# mSD-Shield-Mega_v10.net
KiCad netlist of a schematic drawn in EAGLE
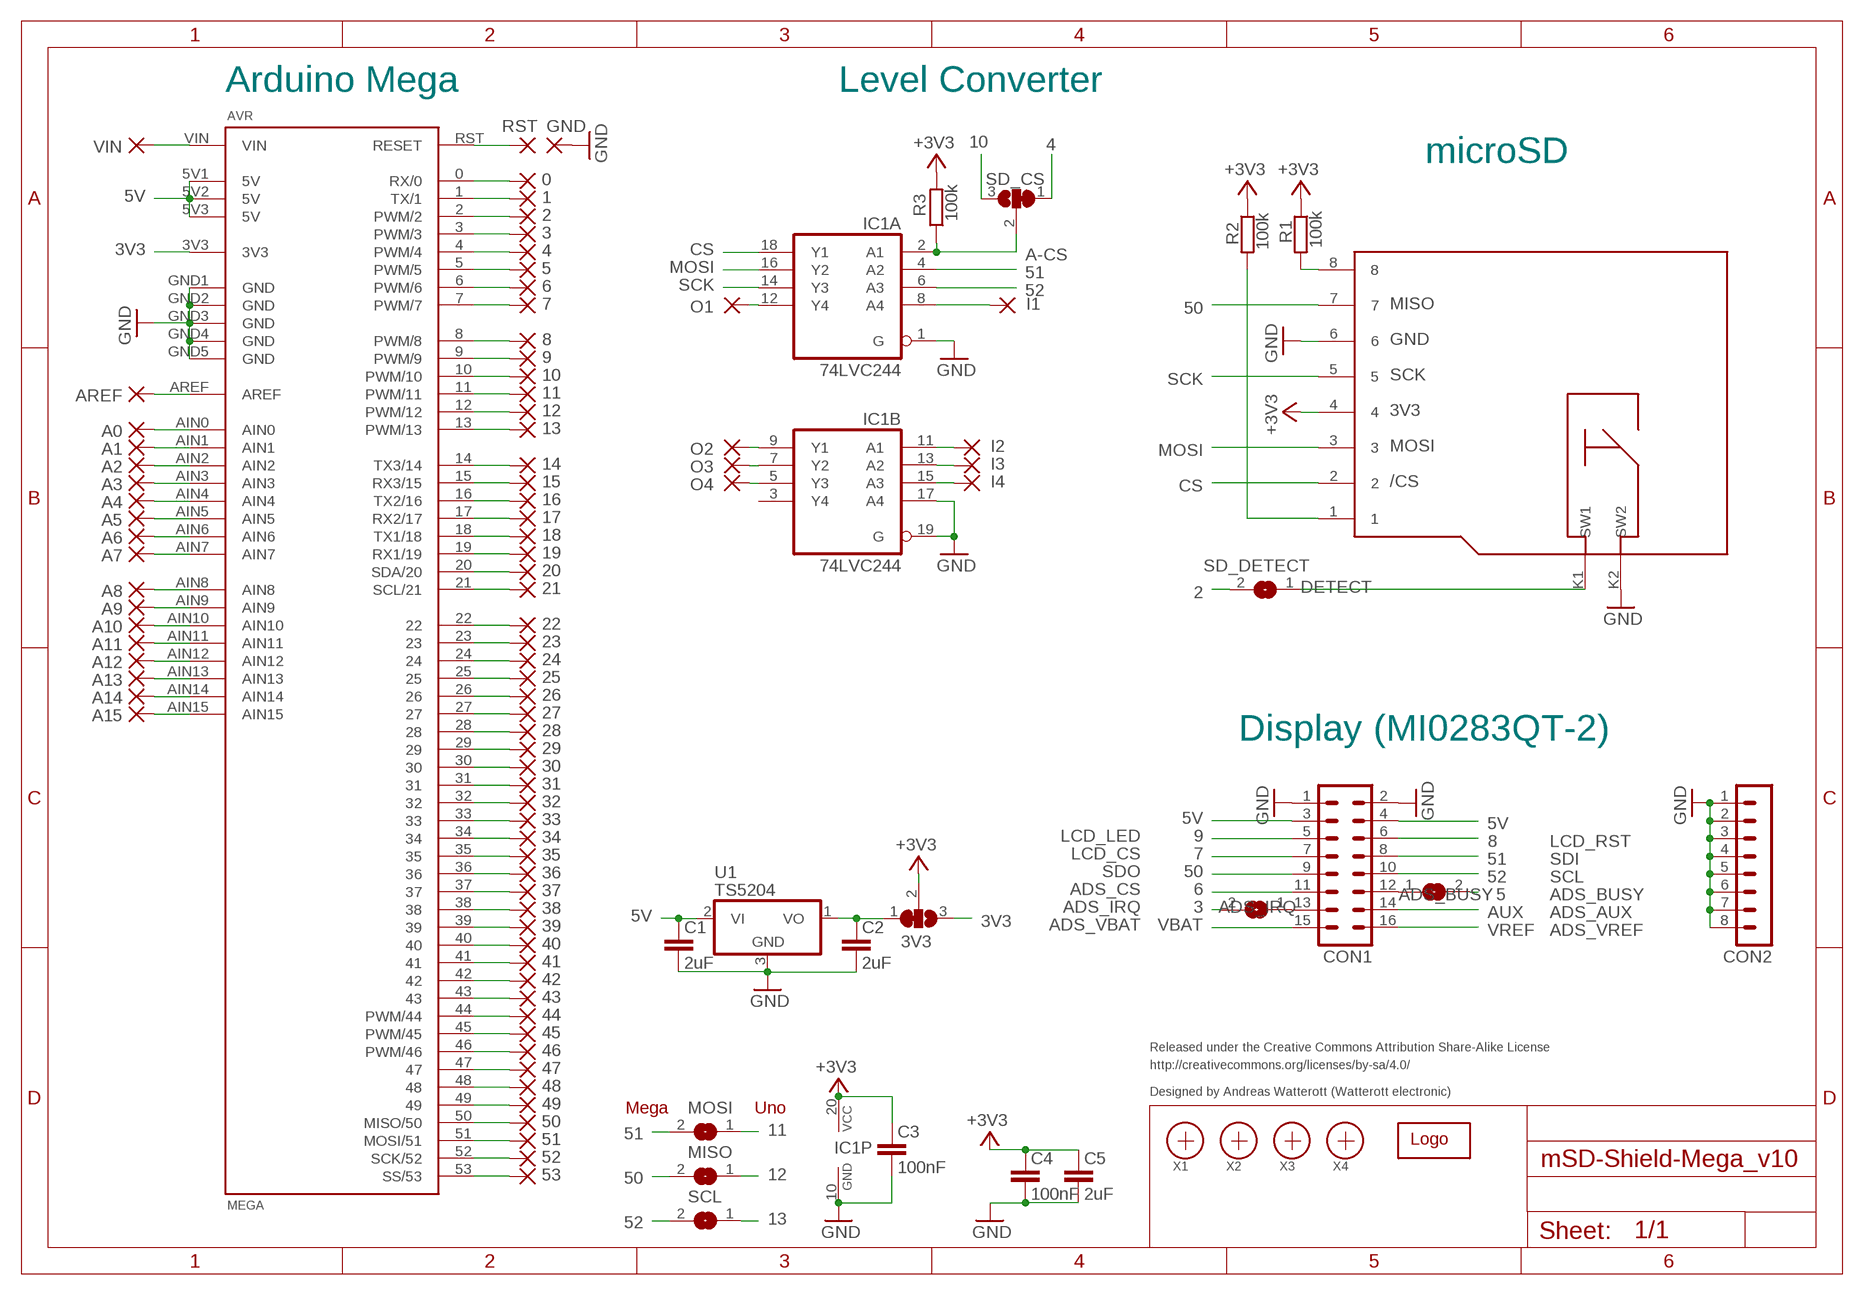
[diagram p0: schematic, sheet 1]

(export (version "E")
  (design (tool "Eeschema 10.0.6"))
  (components
    (comp (ref "0")
      (value "1,6/0,8")
      (footprint "eagle-import:1,6_0,8")
      (libsource (lib "eagle-import") (part "1,6/0,8"))
    )
    (comp (ref "1")
      (value "1,6/0,8")
      (footprint "eagle-import:1,6_0,8")
      (libsource (lib "eagle-import") (part "1,6/0,8"))
    )
    (comp (ref "2")
      (value "1,6/0,8")
      (footprint "eagle-import:1,6_0,8")
      (libsource (lib "eagle-import") (part "1,6/0,8"))
    )
    (comp (ref "3")
      (value "1,6/0,8")
      (footprint "eagle-import:1,6_0,8")
      (libsource (lib "eagle-import") (part "1,6/0,8"))
    )
    (comp (ref "3V3")
      (value "SJ2W")
      (footprint "eagle-import:SJ_2")
      (libsource (lib "eagle-import") (part "SJ2W"))
    )
    (comp (ref "4")
      (value "1,6/0,8")
      (footprint "eagle-import:1,6_0,8")
      (libsource (lib "eagle-import") (part "1,6/0,8"))
    )
    (comp (ref "5")
      (value "1,6/0,8")
      (footprint "eagle-import:1,6_0,8")
      (libsource (lib "eagle-import") (part "1,6/0,8"))
    )
    (comp (ref "6")
      (value "1,6/0,8")
      (footprint "eagle-import:1,6_0,8")
      (libsource (lib "eagle-import") (part "1,6/0,8"))
    )
    (comp (ref "7")
      (value "1,6/0,8")
      (footprint "eagle-import:1,6_0,8")
      (libsource (lib "eagle-import") (part "1,6/0,8"))
    )
    (comp (ref "8")
      (value "1,6/0,8")
      (footprint "eagle-import:1,6_0,8")
      (libsource (lib "eagle-import") (part "1,6/0,8"))
    )
    (comp (ref "9")
      (value "1,6/0,8")
      (footprint "eagle-import:1,6_0,8")
      (libsource (lib "eagle-import") (part "1,6/0,8"))
    )
    (comp (ref "10")
      (value "1,6/0,8")
      (footprint "eagle-import:1,6_0,8")
      (libsource (lib "eagle-import") (part "1,6/0,8"))
    )
    (comp (ref "11")
      (value "1,6/0,8")
      (footprint "eagle-import:1,6_0,8")
      (libsource (lib "eagle-import") (part "1,6/0,8"))
    )
    (comp (ref "12")
      (value "1,6/0,8")
      (footprint "eagle-import:1,6_0,8")
      (libsource (lib "eagle-import") (part "1,6/0,8"))
    )
    (comp (ref "13")
      (value "1,6/0,8")
      (footprint "eagle-import:1,6_0,8")
      (libsource (lib "eagle-import") (part "1,6/0,8"))
    )
    (comp (ref "14")
      (value "1,6/0,8")
      (footprint "eagle-import:1,6_0,8")
      (libsource (lib "eagle-import") (part "1,6/0,8"))
    )
    (comp (ref "15")
      (value "1,6/0,8")
      (footprint "eagle-import:1,6_0,8")
      (libsource (lib "eagle-import") (part "1,6/0,8"))
    )
    (comp (ref "16")
      (value "1,6/0,8")
      (footprint "eagle-import:1,6_0,8")
      (libsource (lib "eagle-import") (part "1,6/0,8"))
    )
    (comp (ref "17")
      (value "1,6/0,8")
      (footprint "eagle-import:1,6_0,8")
      (libsource (lib "eagle-import") (part "1,6/0,8"))
    )
    (comp (ref "18")
      (value "1,6/0,8")
      (footprint "eagle-import:1,6_0,8")
      (libsource (lib "eagle-import") (part "1,6/0,8"))
    )
    (comp (ref "19")
      (value "1,6/0,8")
      (footprint "eagle-import:1,6_0,8")
      (libsource (lib "eagle-import") (part "1,6/0,8"))
    )
    (comp (ref "20")
      (value "1,6/0,8")
      (footprint "eagle-import:1,6_0,8")
      (libsource (lib "eagle-import") (part "1,6/0,8"))
    )
    (comp (ref "21")
      (value "1,6/0,8")
      (footprint "eagle-import:1,6_0,8")
      (libsource (lib "eagle-import") (part "1,6/0,8"))
    )
    (comp (ref "22")
      (value "1,6/0,8")
      (footprint "eagle-import:1,6_0,8")
      (libsource (lib "eagle-import") (part "1,6/0,8"))
    )
    (comp (ref "23")
      (value "1,6/0,8")
      (footprint "eagle-import:1,6_0,8")
      (libsource (lib "eagle-import") (part "1,6/0,8"))
    )
    (comp (ref "24")
      (value "1,6/0,8")
      (footprint "eagle-import:1,6_0,8")
      (libsource (lib "eagle-import") (part "1,6/0,8"))
    )
    (comp (ref "25")
      (value "1,6/0,8")
      (footprint "eagle-import:1,6_0,8")
      (libsource (lib "eagle-import") (part "1,6/0,8"))
    )
    (comp (ref "26")
      (value "1,6/0,8")
      (footprint "eagle-import:1,6_0,8")
      (libsource (lib "eagle-import") (part "1,6/0,8"))
    )
    (comp (ref "27")
      (value "1,6/0,8")
      (footprint "eagle-import:1,6_0,8")
      (libsource (lib "eagle-import") (part "1,6/0,8"))
    )
    (comp (ref "28")
      (value "1,6/0,8")
      (footprint "eagle-import:1,6_0,8")
      (libsource (lib "eagle-import") (part "1,6/0,8"))
    )
    (comp (ref "29")
      (value "1,6/0,8")
      (footprint "eagle-import:1,6_0,8")
      (libsource (lib "eagle-import") (part "1,6/0,8"))
    )
    (comp (ref "30")
      (value "1,6/0,8")
      (footprint "eagle-import:1,6_0,8")
      (libsource (lib "eagle-import") (part "1,6/0,8"))
    )
    (comp (ref "31")
      (value "1,6/0,8")
      (footprint "eagle-import:1,6_0,8")
      (libsource (lib "eagle-import") (part "1,6/0,8"))
    )
    (comp (ref "32")
      (value "1,6/0,8")
      (footprint "eagle-import:1,6_0,8")
      (libsource (lib "eagle-import") (part "1,6/0,8"))
    )
    (comp (ref "33")
      (value "1,6/0,8")
      (footprint "eagle-import:1,6_0,8")
      (libsource (lib "eagle-import") (part "1,6/0,8"))
    )
    (comp (ref "34")
      (value "1,6/0,8")
      (footprint "eagle-import:1,6_0,8")
      (libsource (lib "eagle-import") (part "1,6/0,8"))
    )
    (comp (ref "35")
      (value "1,6/0,8")
      (footprint "eagle-import:1,6_0,8")
      (libsource (lib "eagle-import") (part "1,6/0,8"))
    )
    (comp (ref "36")
      (value "1,6/0,8")
      (footprint "eagle-import:1,6_0,8")
      (libsource (lib "eagle-import") (part "1,6/0,8"))
    )
    (comp (ref "37")
      (value "1,6/0,8")
      (footprint "eagle-import:1,6_0,8")
      (libsource (lib "eagle-import") (part "1,6/0,8"))
    )
    (comp (ref "38")
      (value "1,6/0,8")
      (footprint "eagle-import:1,6_0,8")
      (libsource (lib "eagle-import") (part "1,6/0,8"))
    )
    (comp (ref "39")
      (value "1,6/0,8")
      (footprint "eagle-import:1,6_0,8")
      (libsource (lib "eagle-import") (part "1,6/0,8"))
    )
    (comp (ref "40")
      (value "1,6/0,8")
      (footprint "eagle-import:1,6_0,8")
      (libsource (lib "eagle-import") (part "1,6/0,8"))
    )
    (comp (ref "41")
      (value "1,6/0,8")
      (footprint "eagle-import:1,6_0,8")
      (libsource (lib "eagle-import") (part "1,6/0,8"))
    )
    (comp (ref "42")
      (value "1,6/0,8")
      (footprint "eagle-import:1,6_0,8")
      (libsource (lib "eagle-import") (part "1,6/0,8"))
    )
    (comp (ref "43")
      (value "1,6/0,8")
      (footprint "eagle-import:1,6_0,8")
      (libsource (lib "eagle-import") (part "1,6/0,8"))
    )
    (comp (ref "44")
      (value "1,6/0,8")
      (footprint "eagle-import:1,6_0,8")
      (libsource (lib "eagle-import") (part "1,6/0,8"))
    )
    (comp (ref "45")
      (value "1,6/0,8")
      (footprint "eagle-import:1,6_0,8")
      (libsource (lib "eagle-import") (part "1,6/0,8"))
    )
    (comp (ref "46")
      (value "1,6/0,8")
      (footprint "eagle-import:1,6_0,8")
      (libsource (lib "eagle-import") (part "1,6/0,8"))
    )
    (comp (ref "47")
      (value "1,6/0,8")
      (footprint "eagle-import:1,6_0,8")
      (libsource (lib "eagle-import") (part "1,6/0,8"))
    )
    (comp (ref "48")
      (value "1,6/0,8")
      (footprint "eagle-import:1,6_0,8")
      (libsource (lib "eagle-import") (part "1,6/0,8"))
    )
    (comp (ref "49")
      (value "1,6/0,8")
      (footprint "eagle-import:1,6_0,8")
      (libsource (lib "eagle-import") (part "1,6/0,8"))
    )
    (comp (ref "50")
      (value "1,6/0,8")
      (footprint "eagle-import:1,6_0,8")
      (libsource (lib "eagle-import") (part "1,6/0,8"))
    )
    (comp (ref "51")
      (value "1,6/0,8")
      (footprint "eagle-import:1,6_0,8")
      (libsource (lib "eagle-import") (part "1,6/0,8"))
    )
    (comp (ref "52")
      (value "1,6/0,8")
      (footprint "eagle-import:1,6_0,8")
      (libsource (lib "eagle-import") (part "1,6/0,8"))
    )
    (comp (ref "53")
      (value "1,6/0,8")
      (footprint "eagle-import:1,6_0,8")
      (libsource (lib "eagle-import") (part "1,6/0,8"))
    )
    (comp (ref "A0")
      (value "1,6/0,8")
      (footprint "eagle-import:1,6_0,8")
      (libsource (lib "eagle-import") (part "1,6/0,8"))
    )
    (comp (ref "A1")
      (value "1,6/0,8")
      (footprint "eagle-import:1,6_0,8")
      (libsource (lib "eagle-import") (part "1,6/0,8"))
    )
    (comp (ref "A2")
      (value "1,6/0,8")
      (footprint "eagle-import:1,6_0,8")
      (libsource (lib "eagle-import") (part "1,6/0,8"))
    )
    (comp (ref "A3")
      (value "1,6/0,8")
      (footprint "eagle-import:1,6_0,8")
      (libsource (lib "eagle-import") (part "1,6/0,8"))
    )
    (comp (ref "A4")
      (value "1,6/0,8")
      (footprint "eagle-import:1,6_0,8")
      (libsource (lib "eagle-import") (part "1,6/0,8"))
    )
    (comp (ref "A5")
      (value "1,6/0,8")
      (footprint "eagle-import:1,6_0,8")
      (libsource (lib "eagle-import") (part "1,6/0,8"))
    )
    (comp (ref "A6")
      (value "1,6/0,8")
      (footprint "eagle-import:1,6_0,8")
      (libsource (lib "eagle-import") (part "1,6/0,8"))
    )
    (comp (ref "A7")
      (value "1,6/0,8")
      (footprint "eagle-import:1,6_0,8")
      (libsource (lib "eagle-import") (part "1,6/0,8"))
    )
    (comp (ref "A8")
      (value "1,6/0,8")
      (footprint "eagle-import:1,6_0,8")
      (libsource (lib "eagle-import") (part "1,6/0,8"))
    )
    (comp (ref "A9")
      (value "1,6/0,8")
      (footprint "eagle-import:1,6_0,8")
      (libsource (lib "eagle-import") (part "1,6/0,8"))
    )
    (comp (ref "A10")
      (value "1,6/0,8")
      (footprint "eagle-import:1,6_0,8")
      (libsource (lib "eagle-import") (part "1,6/0,8"))
    )
    (comp (ref "A11")
      (value "1,6/0,8")
      (footprint "eagle-import:1,6_0,8")
      (libsource (lib "eagle-import") (part "1,6/0,8"))
    )
    (comp (ref "A12")
      (value "1,6/0,8")
      (footprint "eagle-import:1,6_0,8")
      (libsource (lib "eagle-import") (part "1,6/0,8"))
    )
    (comp (ref "A13")
      (value "1,6/0,8")
      (footprint "eagle-import:1,6_0,8")
      (libsource (lib "eagle-import") (part "1,6/0,8"))
    )
    (comp (ref "A14")
      (value "1,6/0,8")
      (footprint "eagle-import:1,6_0,8")
      (libsource (lib "eagle-import") (part "1,6/0,8"))
    )
    (comp (ref "A15")
      (value "1,6/0,8")
      (footprint "eagle-import:1,6_0,8")
      (libsource (lib "eagle-import") (part "1,6/0,8"))
    )
    (comp (ref "ADS_BUSY")
      (value "SJ")
      (footprint "eagle-import:SJ")
      (libsource (lib "eagle-import") (part "SJ"))
    )
    (comp (ref "ADS_IRQ")
      (value "SJ")
      (footprint "eagle-import:SJ")
      (libsource (lib "eagle-import") (part "SJ"))
    )
    (comp (ref "AREF")
      (value "1,6/0,8")
      (footprint "eagle-import:1,6_0,8")
      (libsource (lib "eagle-import") (part "1,6/0,8"))
    )
    (comp (ref "AVR")
      (value "MEGA")
      (footprint "eagle-import:MEGA")
      (libsource (lib "eagle-import") (part "MEGA"))
    )
    (comp (ref "C1")
      (value "2uF")
      (footprint "eagle-import:C0805")
      (libsource (lib "eagle-import") (part "C-EUC0805"))
    )
    (comp (ref "C2")
      (value "2uF")
      (footprint "eagle-import:C0805")
      (libsource (lib "eagle-import") (part "C-EUC0805"))
    )
    (comp (ref "C3")
      (value "100nF")
      (footprint "eagle-import:C0603")
      (libsource (lib "eagle-import") (part "C-EUC0603"))
    )
    (comp (ref "C4")
      (value "100nF")
      (footprint "eagle-import:C0603")
      (libsource (lib "eagle-import") (part "C-EUC0603"))
    )
    (comp (ref "C5")
      (value "2uF")
      (footprint "eagle-import:C0603")
      (libsource (lib "eagle-import") (part "C-EUC0603"))
    )
    (comp (ref "CON1")
      (value "MA08-2")
      (footprint "eagle-import:MA08-2")
      (libsource (lib "eagle-import") (part "MA08-2"))
    )
    (comp (ref "CON2")
      (value "MA08-1")
      (footprint "eagle-import:MA08-1")
      (libsource (lib "eagle-import") (part "MA08-1"))
    )
    (comp (ref "GND")
      (value "SMD2")
      (footprint "eagle-import:SMD1,27-2,54")
      (libsource (lib "eagle-import") (part "SMD2"))
    )
    (comp (ref "I1")
      (value "SMD2")
      (footprint "eagle-import:SMD1,27-2,54")
      (libsource (lib "eagle-import") (part "SMD2"))
    )
    (comp (ref "I2")
      (value "SMD2")
      (footprint "eagle-import:SMD1,27-2,54")
      (libsource (lib "eagle-import") (part "SMD2"))
    )
    (comp (ref "I3")
      (value "SMD2")
      (footprint "eagle-import:SMD1,27-2,54")
      (libsource (lib "eagle-import") (part "SMD2"))
    )
    (comp (ref "I4")
      (value "SMD2")
      (footprint "eagle-import:SMD1,27-2,54")
      (libsource (lib "eagle-import") (part "SMD2"))
    )
    (comp (ref "IC1")
      (value "74LVC244")
      (footprint "eagle-import:SO20W")
      (libsource (lib "eagle-import") (part "74244DWHC"))
    )
    (comp (ref "MISO")
      (value "SJ")
      (footprint "eagle-import:SJ")
      (libsource (lib "eagle-import") (part "SJ"))
    )
    (comp (ref "MOSI")
      (value "SJ")
      (footprint "eagle-import:SJ")
      (libsource (lib "eagle-import") (part "SJ"))
    )
    (comp (ref "O1")
      (value "SMD2")
      (footprint "eagle-import:SMD1,27-2,54")
      (libsource (lib "eagle-import") (part "SMD2"))
    )
    (comp (ref "O2")
      (value "SMD2")
      (footprint "eagle-import:SMD1,27-2,54")
      (libsource (lib "eagle-import") (part "SMD2"))
    )
    (comp (ref "O3")
      (value "SMD2")
      (footprint "eagle-import:SMD1,27-2,54")
      (libsource (lib "eagle-import") (part "SMD2"))
    )
    (comp (ref "O4")
      (value "SMD2")
      (footprint "eagle-import:SMD1,27-2,54")
      (libsource (lib "eagle-import") (part "SMD2"))
    )
    (comp (ref "R1")
      (value "100k")
      (footprint "eagle-import:R0603")
      (libsource (lib "eagle-import") (part "R-EU_R0603"))
    )
    (comp (ref "R2")
      (value "100k")
      (footprint "eagle-import:R0603")
      (libsource (lib "eagle-import") (part "R-EU_R0603"))
    )
    (comp (ref "R3")
      (value "100k")
      (footprint "eagle-import:R0603")
      (libsource (lib "eagle-import") (part "R-EU_R0603"))
    )
    (comp (ref "RST")
      (value "SMD2")
      (footprint "eagle-import:SMD1,27-2,54")
      (libsource (lib "eagle-import") (part "SMD2"))
    )
    (comp (ref "SCL") (value "SJ") (footprint "eagle-import:SJ") (libsource (lib "eagle-import") (part "SJ")))
    (comp (ref "SD_CS")
      (value "SJ2W")
      (footprint "eagle-import:SJ_2")
      (libsource (lib "eagle-import") (part "SJ2W"))
    )
    (comp (ref "SD_DETECT")
      (value "SJ")
      (footprint "eagle-import:SJ")
      (libsource (lib "eagle-import") (part "SJ"))
    )
    (comp (ref "U$1")
      (value "WE-LOGO")
      (footprint "eagle-import:WE-LOGO")
      (libsource (lib "eagle-import") (part "WE-LOGO"))
    )
    (comp (ref "U1")
      (value "TS5204")
      (footprint "eagle-import:SOT23")
      (libsource (lib "eagle-import") (part "TS5204"))
    )
    (comp (ref "VIN")
      (value "1,6/0,8")
      (footprint "eagle-import:1,6_0,8")
      (libsource (lib "eagle-import") (part "1,6/0,8"))
    )
    (comp (ref "X1")
      (value "PASSER")
      (footprint "eagle-import:PASSER")
      (libsource (lib "eagle-import") (part "PASSER"))
    )
    (comp (ref "X2")
      (value "PASSER")
      (footprint "eagle-import:PASSER")
      (libsource (lib "eagle-import") (part "PASSER"))
    )
    (comp (ref "X3")
      (value "PASSER")
      (footprint "eagle-import:PASSER")
      (libsource (lib "eagle-import") (part "PASSER"))
    )
    (comp (ref "X4")
      (value "PASSER")
      (footprint "eagle-import:PASSER")
      (libsource (lib "eagle-import") (part "PASSER"))
    )
    (comp (ref "X5")
      (value "MICRO-SD")
      (footprint "eagle-import:MICRO-SD")
      (libsource (lib "eagle-import") (part "MICRO-SD"))
    )
  )
  (nets
    (net (code "1") (name "+3V3") (class "Default")
      (node (ref "3V3") (pin "2") (pinfunction "2_2") (pintype "passive"))
      (node (ref "C3") (pin "1") (pinfunction "1_1") (pintype "passive"))
      (node (ref "C4") (pin "1") (pinfunction "1_1") (pintype "passive"))
      (node (ref "C5") (pin "1") (pinfunction "1_1") (pintype "passive"))
      (node (ref "IC1") (pin "20") (pinfunction "VCC_20") (pintype "power_in"))
      (node (ref "R1") (pin "1") (pinfunction "1_1") (pintype "passive"))
      (node (ref "R2") (pin "1") (pinfunction "1_1") (pintype "passive"))
      (node (ref "R3") (pin "2") (pinfunction "2_2") (pintype "passive"))
      (node (ref "X5") (pin "4") (pinfunction "4_4") (pintype "bidirectional"))
    )
    (net (code "2") (name "/2") (class "Default")
      (node (ref "2") (pin "1") (pinfunction "P_1") (pintype "passive"))
      (node (ref "AVR") (pin "2") (pinfunction "PWM/2_2") (pintype "bidirectional"))
      (node (ref "SD_DETECT") (pin "2") (pinfunction "2_2") (pintype "passive"))
    )
    (net (code "3") (name "/3") (class "Default")
      (node (ref "3") (pin "1") (pinfunction "P_1") (pintype "passive"))
      (node (ref "ADS_IRQ") (pin "2") (pinfunction "2_2") (pintype "passive"))
      (node (ref "AVR") (pin "3") (pinfunction "PWM/3_3") (pintype "bidirectional"))
    )
    (net (code "4") (name "/3V3") (class "Default")
      (node (ref "3V3") (pin "3") (pinfunction "3_3") (pintype "passive"))
      (node (ref "AVR") (pin "3V3") (pinfunction "3V3_3V3") (pintype "power_in"))
    )
    (net (code "5") (name "/4") (class "Default")
      (node (ref "4") (pin "1") (pinfunction "P_1") (pintype "passive"))
      (node (ref "AVR") (pin "4") (pinfunction "PWM/4_4") (pintype "bidirectional"))
      (node (ref "SD_CS") (pin "1") (pinfunction "1_1") (pintype "passive"))
    )
    (net (code "6") (name "/5") (class "Default")
      (node (ref "5") (pin "1") (pinfunction "P_1") (pintype "passive"))
      (node (ref "ADS_BUSY") (pin "2") (pinfunction "2_2") (pintype "passive"))
      (node (ref "AVR") (pin "5") (pinfunction "PWM/5_5") (pintype "bidirectional"))
    )
    (net (code "7") (name "/5V") (class "Default")
      (node (ref "AVR") (pin "5V1") (pinfunction "5V_5V1") (pintype "power_in"))
      (node (ref "AVR") (pin "5V2") (pinfunction "5V_5V2") (pintype "power_in"))
      (node (ref "AVR") (pin "5V3") (pinfunction "5V_5V3") (pintype "power_in"))
      (node (ref "C1") (pin "1") (pinfunction "1_1") (pintype "passive"))
      (node (ref "CON1") (pin "3") (pinfunction "3_3") (pintype "passive"))
      (node (ref "CON1") (pin "4") (pinfunction "4_4") (pintype "passive"))
      (node (ref "U1") (pin "2") (pinfunction "VI_2") (pintype "input"))
    )
    (net (code "8") (name "/6") (class "Default")
      (node (ref "6") (pin "1") (pinfunction "P_1") (pintype "passive"))
      (node (ref "AVR") (pin "6") (pinfunction "PWM/6_6") (pintype "bidirectional"))
      (node (ref "CON1") (pin "11") (pinfunction "11_11") (pintype "passive"))
    )
    (net (code "9") (name "/7") (class "Default")
      (node (ref "7") (pin "1") (pinfunction "P_1") (pintype "passive"))
      (node (ref "AVR") (pin "7") (pinfunction "PWM/7_7") (pintype "bidirectional"))
      (node (ref "CON1") (pin "7") (pinfunction "7_7") (pintype "passive"))
    )
    (net (code "10") (name "/8") (class "Default")
      (node (ref "8") (pin "1") (pinfunction "P_1") (pintype "passive"))
      (node (ref "AVR") (pin "8") (pinfunction "PWM/8_8") (pintype "bidirectional"))
      (node (ref "CON1") (pin "6") (pinfunction "6_6") (pintype "passive"))
    )
    (net (code "11") (name "/9") (class "Default")
      (node (ref "9") (pin "1") (pinfunction "P_1") (pintype "passive"))
      (node (ref "AVR") (pin "9") (pinfunction "PWM/9_9") (pintype "bidirectional"))
      (node (ref "CON1") (pin "5") (pinfunction "5_5") (pintype "passive"))
    )
    (net (code "12") (name "/10") (class "Default")
      (node (ref "10") (pin "1") (pinfunction "P_1") (pintype "passive"))
      (node (ref "AVR") (pin "10") (pinfunction "PWM/10_10") (pintype "bidirectional"))
      (node (ref "SD_CS") (pin "3") (pinfunction "3_3") (pintype "passive"))
    )
    (net (code "13") (name "/11") (class "Default")
      (node (ref "11") (pin "1") (pinfunction "P_1") (pintype "passive"))
      (node (ref "AVR") (pin "11") (pinfunction "PWM/11_11") (pintype "bidirectional"))
      (node (ref "MOSI") (pin "1") (pinfunction "1_1") (pintype "passive"))
    )
    (net (code "14") (name "/12") (class "Default")
      (node (ref "12") (pin "1") (pinfunction "P_1") (pintype "passive"))
      (node (ref "AVR") (pin "12") (pinfunction "PWM/12_12") (pintype "bidirectional"))
      (node (ref "MISO") (pin "1") (pinfunction "1_1") (pintype "passive"))
    )
    (net (code "15") (name "/13") (class "Default")
      (node (ref "13") (pin "1") (pinfunction "P_1") (pintype "passive"))
      (node (ref "AVR") (pin "13") (pinfunction "PWM/13_13") (pintype "bidirectional"))
      (node (ref "SCL") (pin "1") (pinfunction "1_1") (pintype "passive"))
    )
    (net (code "16") (name "/50") (class "Default")
      (node (ref "50") (pin "1") (pinfunction "P_1") (pintype "passive"))
      (node (ref "AVR") (pin "50") (pinfunction "MISO/50_50") (pintype "bidirectional"))
      (node (ref "CON1") (pin "9") (pinfunction "9_9") (pintype "passive"))
      (node (ref "MISO") (pin "2") (pinfunction "2_2") (pintype "passive"))
      (node (ref "X5") (pin "7") (pinfunction "7_7") (pintype "bidirectional"))
    )
    (net (code "17") (name "/51") (class "Default")
      (node (ref "51") (pin "1") (pinfunction "P_1") (pintype "passive"))
      (node (ref "AVR") (pin "51") (pinfunction "MOSI/51_51") (pintype "bidirectional"))
      (node (ref "CON1") (pin "8") (pinfunction "8_8") (pintype "passive"))
      (node (ref "IC1") (pin "4") (pinfunction "A2_4") (pintype "input"))
      (node (ref "MOSI") (pin "2") (pinfunction "2_2") (pintype "passive"))
    )
    (net (code "18") (name "/52") (class "Default")
      (node (ref "52") (pin "1") (pinfunction "P_1") (pintype "passive"))
      (node (ref "AVR") (pin "52") (pinfunction "SCK/52_52") (pintype "bidirectional"))
      (node (ref "CON1") (pin "10") (pinfunction "10_10") (pintype "passive"))
      (node (ref "IC1") (pin "6") (pinfunction "A3_6") (pintype "input"))
      (node (ref "SCL") (pin "2") (pinfunction "2_2") (pintype "passive"))
    )
    (net (code "19") (name "/A-CS") (class "Default")
      (node (ref "IC1") (pin "2") (pinfunction "A1_2") (pintype "input"))
      (node (ref "R3") (pin "1") (pinfunction "1_1") (pintype "passive"))
      (node (ref "SD_CS") (pin "2") (pinfunction "2_2") (pintype "passive"))
    )
    (net (code "20") (name "/AUX") (class "Default")
      (node (ref "CON1") (pin "14") (pinfunction "14_14") (pintype "passive"))
    )
    (net (code "21") (name "/CS") (class "Default")
      (node (ref "IC1") (pin "18") (pinfunction "Y1_18") (pintype "tri_state"))
      (node (ref "X5") (pin "2") (pinfunction "2_2") (pintype "bidirectional"))
    )
    (net (code "22") (name "/DETECT") (class "Default")
      (node (ref "SD_DETECT") (pin "1") (pinfunction "1_1") (pintype "passive"))
      (node (ref "X5") (pin "K1") (pinfunction "SW1_K1") (pintype "bidirectional"))
    )
    (net (code "23") (name "/MOSI") (class "Default")
      (node (ref "IC1") (pin "16") (pinfunction "Y2_16") (pintype "tri_state"))
      (node (ref "X5") (pin "3") (pinfunction "3_3") (pintype "bidirectional"))
    )
    (net (code "24") (name "/SCK") (class "Default")
      (node (ref "IC1") (pin "14") (pinfunction "Y3_14") (pintype "tri_state"))
      (node (ref "X5") (pin "5") (pinfunction "5_5") (pintype "bidirectional"))
    )
    (net (code "25") (name "/VBAT") (class "Default")
      (node (ref "CON1") (pin "15") (pinfunction "15_15") (pintype "passive"))
    )
    (net (code "26") (name "/VREF") (class "Default")
      (node (ref "CON1") (pin "16") (pinfunction "16_16") (pintype "passive"))
    )
    (net (code "27") (name "GND") (class "Default")
      (node (ref "AVR") (pin "GND1") (pinfunction "GND_GND1") (pintype "power_in"))
      (node (ref "AVR") (pin "GND2") (pinfunction "GND_GND2") (pintype "power_in"))
      (node (ref "AVR") (pin "GND3") (pinfunction "GND_GND3") (pintype "power_in"))
      (node (ref "AVR") (pin "GND4") (pinfunction "GND_GND4") (pintype "power_in"))
      (node (ref "AVR") (pin "GND5") (pinfunction "GND_GND5") (pintype "power_in"))
      (node (ref "C1") (pin "2") (pinfunction "2_2") (pintype "passive"))
      (node (ref "C2") (pin "2") (pinfunction "2_2") (pintype "passive"))
      (node (ref "C3") (pin "2") (pinfunction "2_2") (pintype "passive"))
      (node (ref "C4") (pin "2") (pinfunction "2_2") (pintype "passive"))
      (node (ref "C5") (pin "2") (pinfunction "2_2") (pintype "passive"))
      (node (ref "CON1") (pin "1") (pinfunction "1_1") (pintype "passive"))
      (node (ref "CON1") (pin "2") (pinfunction "2_2") (pintype "passive"))
      (node (ref "CON2") (pin "1") (pinfunction "1_1") (pintype "passive"))
      (node (ref "CON2") (pin "2") (pinfunction "2_2") (pintype "passive"))
      (node (ref "CON2") (pin "3") (pinfunction "3_3") (pintype "passive"))
      (node (ref "CON2") (pin "4") (pinfunction "4_4") (pintype "passive"))
      (node (ref "CON2") (pin "5") (pinfunction "5_5") (pintype "passive"))
      (node (ref "CON2") (pin "6") (pinfunction "6_6") (pintype "passive"))
      (node (ref "CON2") (pin "7") (pinfunction "7_7") (pintype "passive"))
      (node (ref "CON2") (pin "8") (pinfunction "8_8") (pintype "passive"))
      (node (ref "GND") (pin "1") (pinfunction "P_1") (pintype "passive"))
      (node (ref "IC1") (pin "1") (pinfunction "G_1") (pintype "input"))
      (node (ref "IC1") (pin "10") (pinfunction "GND_10") (pintype "power_in"))
      (node (ref "IC1") (pin "17") (pinfunction "A4_17") (pintype "input"))
      (node (ref "IC1") (pin "19") (pinfunction "G_19") (pintype "input"))
      (node (ref "U1") (pin "3") (pinfunction "GND_3") (pintype "passive"))
      (node (ref "X5") (pin "6") (pinfunction "6_6") (pintype "bidirectional"))
      (node (ref "X5") (pin "K2") (pinfunction "SW2_K2") (pintype "bidirectional"))
    )
    (net (code "28") (name "Net-(0-P)") (class "Default")
      (node (ref "0") (pin "1") (pinfunction "P_1") (pintype "passive"))
      (node (ref "AVR") (pin "0") (pinfunction "RX/0_0") (pintype "bidirectional"))
    )
    (net (code "29") (name "Net-(1-P)") (class "Default")
      (node (ref "1") (pin "1") (pinfunction "P_1") (pintype "passive"))
      (node (ref "AVR") (pin "1") (pinfunction "TX/1_1") (pintype "bidirectional"))
    )
    (net (code "30") (name "Net-(14-P)") (class "Default")
      (node (ref "14") (pin "1") (pinfunction "P_1") (pintype "passive"))
      (node (ref "AVR") (pin "14") (pinfunction "TX3/14_14") (pintype "bidirectional"))
    )
    (net (code "31") (name "Net-(15-P)") (class "Default")
      (node (ref "15") (pin "1") (pinfunction "P_1") (pintype "passive"))
      (node (ref "AVR") (pin "15") (pinfunction "RX3/15_15") (pintype "bidirectional"))
    )
    (net (code "32") (name "Net-(16-P)") (class "Default")
      (node (ref "16") (pin "1") (pinfunction "P_1") (pintype "passive"))
      (node (ref "AVR") (pin "16") (pinfunction "TX2/16_16") (pintype "bidirectional"))
    )
    (net (code "33") (name "Net-(17-P)") (class "Default")
      (node (ref "17") (pin "1") (pinfunction "P_1") (pintype "passive"))
      (node (ref "AVR") (pin "17") (pinfunction "RX2/17_17") (pintype "bidirectional"))
    )
    (net (code "34") (name "Net-(18-P)") (class "Default")
      (node (ref "18") (pin "1") (pinfunction "P_1") (pintype "passive"))
      (node (ref "AVR") (pin "18") (pinfunction "TX1/18_18") (pintype "bidirectional"))
    )
    (net (code "35") (name "Net-(19-P)") (class "Default")
      (node (ref "19") (pin "1") (pinfunction "P_1") (pintype "passive"))
      (node (ref "AVR") (pin "19") (pinfunction "RX1/19_19") (pintype "bidirectional"))
    )
    (net (code "36") (name "Net-(20-P)") (class "Default")
      (node (ref "20") (pin "1") (pinfunction "P_1") (pintype "passive"))
      (node (ref "AVR") (pin "20") (pinfunction "SDA/20_20") (pintype "bidirectional"))
    )
    (net (code "37") (name "Net-(21-P)") (class "Default")
      (node (ref "21") (pin "1") (pinfunction "P_1") (pintype "passive"))
      (node (ref "AVR") (pin "21") (pinfunction "SCL/21_21") (pintype "bidirectional"))
    )
    (net (code "38") (name "Net-(22-P)") (class "Default")
      (node (ref "22") (pin "1") (pinfunction "P_1") (pintype "passive"))
      (node (ref "AVR") (pin "22") (pinfunction "22_22") (pintype "bidirectional"))
    )
    (net (code "39") (name "Net-(23-P)") (class "Default")
      (node (ref "23") (pin "1") (pinfunction "P_1") (pintype "passive"))
      (node (ref "AVR") (pin "23") (pinfunction "23_23") (pintype "bidirectional"))
    )
    (net (code "40") (name "Net-(24-P)") (class "Default")
      (node (ref "24") (pin "1") (pinfunction "P_1") (pintype "passive"))
      (node (ref "AVR") (pin "24") (pinfunction "24_24") (pintype "bidirectional"))
    )
    (net (code "41") (name "Net-(25-P)") (class "Default")
      (node (ref "25") (pin "1") (pinfunction "P_1") (pintype "passive"))
      (node (ref "AVR") (pin "25") (pinfunction "25_25") (pintype "bidirectional"))
    )
    (net (code "42") (name "Net-(26-P)") (class "Default")
      (node (ref "26") (pin "1") (pinfunction "P_1") (pintype "passive"))
      (node (ref "AVR") (pin "26") (pinfunction "26_26") (pintype "bidirectional"))
    )
    (net (code "43") (name "Net-(27-P)") (class "Default")
      (node (ref "27") (pin "1") (pinfunction "P_1") (pintype "passive"))
      (node (ref "AVR") (pin "27") (pinfunction "27_27") (pintype "bidirectional"))
    )
    (net (code "44") (name "Net-(28-P)") (class "Default")
      (node (ref "28") (pin "1") (pinfunction "P_1") (pintype "passive"))
      (node (ref "AVR") (pin "28") (pinfunction "28_28") (pintype "bidirectional"))
    )
    (net (code "45") (name "Net-(29-P)") (class "Default")
      (node (ref "29") (pin "1") (pinfunction "P_1") (pintype "passive"))
      (node (ref "AVR") (pin "29") (pinfunction "29_29") (pintype "bidirectional"))
    )
    (net (code "46") (name "Net-(30-P)") (class "Default")
      (node (ref "30") (pin "1") (pinfunction "P_1") (pintype "passive"))
      (node (ref "AVR") (pin "30") (pinfunction "30_30") (pintype "bidirectional"))
    )
    (net (code "47") (name "Net-(31-P)") (class "Default")
      (node (ref "31") (pin "1") (pinfunction "P_1") (pintype "passive"))
      (node (ref "AVR") (pin "31") (pinfunction "31_31") (pintype "bidirectional"))
    )
    (net (code "48") (name "Net-(32-P)") (class "Default")
      (node (ref "32") (pin "1") (pinfunction "P_1") (pintype "passive"))
      (node (ref "AVR") (pin "32") (pinfunction "32_32") (pintype "bidirectional"))
    )
    (net (code "49") (name "Net-(33-P)") (class "Default")
      (node (ref "33") (pin "1") (pinfunction "P_1") (pintype "passive"))
      (node (ref "AVR") (pin "33") (pinfunction "33_33") (pintype "bidirectional"))
    )
    (net (code "50") (name "Net-(34-P)") (class "Default")
      (node (ref "34") (pin "1") (pinfunction "P_1") (pintype "passive"))
      (node (ref "AVR") (pin "34") (pinfunction "34_34") (pintype "bidirectional"))
    )
    (net (code "51") (name "Net-(35-P)") (class "Default")
      (node (ref "35") (pin "1") (pinfunction "P_1") (pintype "passive"))
      (node (ref "AVR") (pin "35") (pinfunction "35_35") (pintype "bidirectional"))
    )
    (net (code "52") (name "Net-(36-P)") (class "Default")
      (node (ref "36") (pin "1") (pinfunction "P_1") (pintype "passive"))
      (node (ref "AVR") (pin "36") (pinfunction "36_36") (pintype "bidirectional"))
    )
    (net (code "53") (name "Net-(37-P)") (class "Default")
      (node (ref "37") (pin "1") (pinfunction "P_1") (pintype "passive"))
      (node (ref "AVR") (pin "37") (pinfunction "37_37") (pintype "bidirectional"))
    )
    (net (code "54") (name "Net-(38-P)") (class "Default")
      (node (ref "38") (pin "1") (pinfunction "P_1") (pintype "passive"))
      (node (ref "AVR") (pin "38") (pinfunction "38_38") (pintype "bidirectional"))
    )
    (net (code "55") (name "Net-(39-P)") (class "Default")
      (node (ref "39") (pin "1") (pinfunction "P_1") (pintype "passive"))
      (node (ref "AVR") (pin "39") (pinfunction "39_39") (pintype "bidirectional"))
    )
    (net (code "56") (name "Net-(40-P)") (class "Default")
      (node (ref "40") (pin "1") (pinfunction "P_1") (pintype "passive"))
      (node (ref "AVR") (pin "40") (pinfunction "40_40") (pintype "bidirectional"))
    )
    (net (code "57") (name "Net-(41-P)") (class "Default")
      (node (ref "41") (pin "1") (pinfunction "P_1") (pintype "passive"))
      (node (ref "AVR") (pin "41") (pinfunction "41_41") (pintype "bidirectional"))
    )
    (net (code "58") (name "Net-(42-P)") (class "Default")
      (node (ref "42") (pin "1") (pinfunction "P_1") (pintype "passive"))
      (node (ref "AVR") (pin "42") (pinfunction "42_42") (pintype "bidirectional"))
    )
    (net (code "59") (name "Net-(43-P)") (class "Default")
      (node (ref "43") (pin "1") (pinfunction "P_1") (pintype "passive"))
      (node (ref "AVR") (pin "43") (pinfunction "43_43") (pintype "bidirectional"))
    )
    (net (code "60") (name "Net-(44-P)") (class "Default")
      (node (ref "44") (pin "1") (pinfunction "P_1") (pintype "passive"))
      (node (ref "AVR") (pin "44") (pinfunction "PWM/44_44") (pintype "bidirectional"))
    )
    (net (code "61") (name "Net-(45-P)") (class "Default")
      (node (ref "45") (pin "1") (pinfunction "P_1") (pintype "passive"))
      (node (ref "AVR") (pin "45") (pinfunction "PWM/45_45") (pintype "bidirectional"))
    )
    (net (code "62") (name "Net-(46-P)") (class "Default")
      (node (ref "46") (pin "1") (pinfunction "P_1") (pintype "passive"))
      (node (ref "AVR") (pin "46") (pinfunction "PWM/46_46") (pintype "bidirectional"))
    )
    (net (code "63") (name "Net-(47-P)") (class "Default")
      (node (ref "47") (pin "1") (pinfunction "P_1") (pintype "passive"))
      (node (ref "AVR") (pin "47") (pinfunction "47_47") (pintype "bidirectional"))
    )
    (net (code "64") (name "Net-(48-P)") (class "Default")
      (node (ref "48") (pin "1") (pinfunction "P_1") (pintype "passive"))
      (node (ref "AVR") (pin "48") (pinfunction "48_48") (pintype "bidirectional"))
    )
    (net (code "65") (name "Net-(49-P)") (class "Default")
      (node (ref "49") (pin "1") (pinfunction "P_1") (pintype "passive"))
      (node (ref "AVR") (pin "49") (pinfunction "49_49") (pintype "bidirectional"))
    )
    (net (code "66") (name "Net-(53-P)") (class "Default")
      (node (ref "53") (pin "1") (pinfunction "P_1") (pintype "passive"))
      (node (ref "AVR") (pin "53") (pinfunction "SS/53_53") (pintype "bidirectional"))
    )
    (net (code "67") (name "Net-(A0-P)") (class "Default")
      (node (ref "A0") (pin "1") (pinfunction "P_1") (pintype "passive"))
      (node (ref "AVR") (pin "AIN0") (pinfunction "AIN0_AIN0") (pintype "bidirectional"))
    )
    (net (code "68") (name "Net-(A1-P)") (class "Default")
      (node (ref "A1") (pin "1") (pinfunction "P_1") (pintype "passive"))
      (node (ref "AVR") (pin "AIN1") (pinfunction "AIN1_AIN1") (pintype "bidirectional"))
    )
    (net (code "69") (name "Net-(A2-P)") (class "Default")
      (node (ref "A2") (pin "1") (pinfunction "P_1") (pintype "passive"))
      (node (ref "AVR") (pin "AIN2") (pinfunction "AIN2_AIN2") (pintype "bidirectional"))
    )
    (net (code "70") (name "Net-(A3-P)") (class "Default")
      (node (ref "A3") (pin "1") (pinfunction "P_1") (pintype "passive"))
      (node (ref "AVR") (pin "AIN3") (pinfunction "AIN3_AIN3") (pintype "bidirectional"))
    )
    (net (code "71") (name "Net-(A4-P)") (class "Default")
      (node (ref "A4") (pin "1") (pinfunction "P_1") (pintype "passive"))
      (node (ref "AVR") (pin "AIN4") (pinfunction "AIN4_AIN4") (pintype "bidirectional"))
    )
    (net (code "72") (name "Net-(A5-P)") (class "Default")
      (node (ref "A5") (pin "1") (pinfunction "P_1") (pintype "passive"))
      (node (ref "AVR") (pin "AIN5") (pinfunction "AIN5_AIN5") (pintype "bidirectional"))
    )
    (net (code "73") (name "Net-(A6-P)") (class "Default")
      (node (ref "A6") (pin "1") (pinfunction "P_1") (pintype "passive"))
      (node (ref "AVR") (pin "AIN6") (pinfunction "AIN6_AIN6") (pintype "bidirectional"))
    )
    (net (code "74") (name "Net-(A7-P)") (class "Default")
      (node (ref "A7") (pin "1") (pinfunction "P_1") (pintype "passive"))
      (node (ref "AVR") (pin "AIN7") (pinfunction "AIN7_AIN7") (pintype "bidirectional"))
    )
    (net (code "75") (name "Net-(A8-P)") (class "Default")
      (node (ref "A8") (pin "1") (pinfunction "P_1") (pintype "passive"))
      (node (ref "AVR") (pin "AIN8") (pinfunction "AIN8_AIN8") (pintype "bidirectional"))
    )
    (net (code "76") (name "Net-(A9-P)") (class "Default")
      (node (ref "A9") (pin "1") (pinfunction "P_1") (pintype "passive"))
      (node (ref "AVR") (pin "AIN9") (pinfunction "AIN9_AIN9") (pintype "bidirectional"))
    )
    (net (code "77") (name "Net-(A10-P)") (class "Default")
      (node (ref "A10") (pin "1") (pinfunction "P_1") (pintype "passive"))
      (node (ref "AVR") (pin "AIN10") (pinfunction "AIN10_AIN10") (pintype "bidirectional"))
    )
    (net (code "78") (name "Net-(A11-P)") (class "Default")
      (node (ref "A11") (pin "1") (pinfunction "P_1") (pintype "passive"))
      (node (ref "AVR") (pin "AIN11") (pinfunction "AIN11_AIN11") (pintype "bidirectional"))
    )
    (net (code "79") (name "Net-(A12-P)") (class "Default")
      (node (ref "A12") (pin "1") (pinfunction "P_1") (pintype "passive"))
      (node (ref "AVR") (pin "AIN12") (pinfunction "AIN12_AIN12") (pintype "bidirectional"))
    )
    (net (code "80") (name "Net-(A13-P)") (class "Default")
      (node (ref "A13") (pin "1") (pinfunction "P_1") (pintype "passive"))
      (node (ref "AVR") (pin "AIN13") (pinfunction "AIN13_AIN13") (pintype "bidirectional"))
    )
    (net (code "81") (name "Net-(A14-P)") (class "Default")
      (node (ref "A14") (pin "1") (pinfunction "P_1") (pintype "passive"))
      (node (ref "AVR") (pin "AIN14") (pinfunction "AIN14_AIN14") (pintype "bidirectional"))
    )
    (net (code "82") (name "Net-(A15-P)") (class "Default")
      (node (ref "A15") (pin "1") (pinfunction "P_1") (pintype "passive"))
      (node (ref "AVR") (pin "AIN15") (pinfunction "AIN15_AIN15") (pintype "bidirectional"))
    )
    (net (code "83") (name "Net-(ADS_BUSY-Pad1)") (class "Default")
      (node (ref "ADS_BUSY") (pin "1") (pinfunction "1_1") (pintype "passive"))
      (node (ref "CON1") (pin "12") (pinfunction "12_12") (pintype "passive"))
    )
    (net (code "84") (name "Net-(ADS_IRQ-Pad1)") (class "Default")
      (node (ref "ADS_IRQ") (pin "1") (pinfunction "1_1") (pintype "passive"))
      (node (ref "CON1") (pin "13") (pinfunction "13_13") (pintype "passive"))
    )
    (net (code "85") (name "Net-(AREF-P)") (class "Default")
      (node (ref "AREF") (pin "1") (pinfunction "P_1") (pintype "passive"))
      (node (ref "AVR") (pin "AREF") (pinfunction "AREF_AREF") (pintype "power_in"))
    )
    (net (code "86") (name "Net-(AVR-RESET)") (class "Default")
      (node (ref "AVR") (pin "RST") (pinfunction "RESET_RST") (pintype "bidirectional"))
      (node (ref "RST") (pin "1") (pinfunction "P_1") (pintype "passive"))
    )
    (net (code "87") (name "Net-(I1-P)") (class "Default")
      (node (ref "I1") (pin "1") (pinfunction "P_1") (pintype "passive"))
      (node (ref "IC1") (pin "8") (pinfunction "A4_8") (pintype "input"))
    )
    (net (code "88") (name "Net-(I2-P)") (class "Default")
      (node (ref "I2") (pin "1") (pinfunction "P_1") (pintype "passive"))
      (node (ref "IC1") (pin "11") (pinfunction "A1_11") (pintype "input"))
    )
    (net (code "89") (name "Net-(I3-P)") (class "Default")
      (node (ref "I3") (pin "1") (pinfunction "P_1") (pintype "passive"))
      (node (ref "IC1") (pin "13") (pinfunction "A2_13") (pintype "input"))
    )
    (net (code "90") (name "Net-(I4-P)") (class "Default")
      (node (ref "I4") (pin "1") (pinfunction "P_1") (pintype "passive"))
      (node (ref "IC1") (pin "15") (pinfunction "A3_15") (pintype "input"))
    )
    (net (code "91") (name "Net-(IC1A-Y4)") (class "Default")
      (node (ref "IC1") (pin "12") (pinfunction "Y4_12") (pintype "tri_state"))
      (node (ref "O1") (pin "1") (pinfunction "P_1") (pintype "passive"))
    )
    (net (code "92") (name "Net-(IC1B-Y1)") (class "Default")
      (node (ref "IC1") (pin "9") (pinfunction "Y1_9") (pintype "tri_state"))
      (node (ref "O2") (pin "1") (pinfunction "P_1") (pintype "passive"))
    )
    (net (code "93") (name "Net-(IC1B-Y2)") (class "Default")
      (node (ref "IC1") (pin "7") (pinfunction "Y2_7") (pintype "tri_state"))
      (node (ref "O3") (pin "1") (pinfunction "P_1") (pintype "passive"))
    )
    (net (code "94") (name "Net-(IC1B-Y3)") (class "Default")
      (node (ref "IC1") (pin "5") (pinfunction "Y3_5") (pintype "tri_state"))
      (node (ref "O4") (pin "1") (pinfunction "P_1") (pintype "passive"))
    )
    (net (code "95") (name "Net-(R1-Pad2)") (class "Default")
      (node (ref "R1") (pin "2") (pinfunction "2_2") (pintype "passive"))
      (node (ref "X5") (pin "8") (pinfunction "8_8") (pintype "bidirectional"))
    )
    (net (code "96") (name "Net-(R2-Pad2)") (class "Default")
      (node (ref "R2") (pin "2") (pinfunction "2_2") (pintype "passive"))
      (node (ref "X5") (pin "1") (pinfunction "1_1") (pintype "bidirectional"))
    )
    (net (code "97") (name "Net-(U1-VO)") (class "Default")
      (node (ref "3V3") (pin "1") (pinfunction "1_1") (pintype "passive"))
      (node (ref "C2") (pin "1") (pinfunction "1_1") (pintype "passive"))
      (node (ref "U1") (pin "1") (pinfunction "VO_1") (pintype "passive"))
    )
    (net (code "98") (name "Net-(VIN-P)") (class "Default")
      (node (ref "AVR") (pin "VIN") (pinfunction "VIN_VIN") (pintype "power_in"))
      (node (ref "VIN") (pin "1") (pinfunction "P_1") (pintype "passive"))
    )
    (net (code "99") (name "unconnected-(IC1B-Y4-Pad3)") (class "Default")
      (node (ref "IC1") (pin "3") (pinfunction "Y4_3") (pintype "tri_state"))
    )
  )
)
